# Esquematico_2.net
KiCad netlist of a schematic drawn in Altium Designer
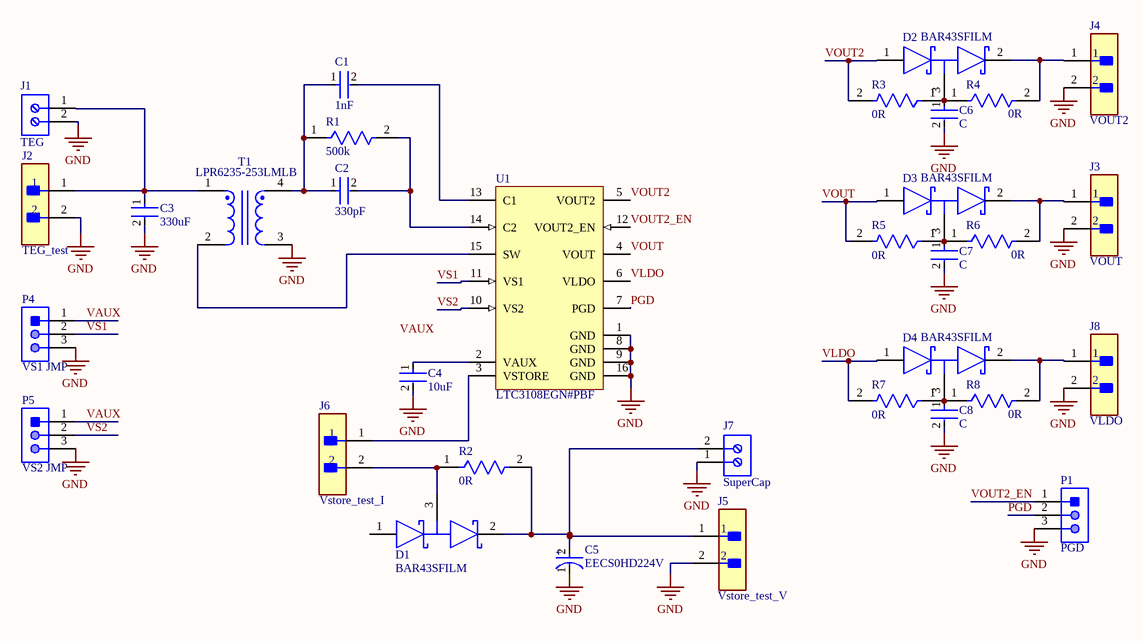
[diagram p0: Esquematico_2.SchDoc]

(export (version "E")
  (design (tool "Eeschema 10.0.6"))
  (components
    (comp (ref "C1")
      (value "1nF")
      (footprint "FP-CL21-IPC_B")
      (description "CL21 Series 0805 22uF 6.3V ±20% Tolerance X5R Multilayer Ceramic Chip Capacitor")
      (fields (field (name "TOLERANCE") "20%"))
      (libsource (lib "Altium Content Vault") (part "b4654b650e69147ec39a6b967a45e02"))
    )
    (comp (ref "C2")
      (value "330pF")
      (footprint "FP-CL21-IPC_B")
      (description "CL21 Series 0805 22uF 6.3V ±20% Tolerance X5R Multilayer Ceramic Chip Capacitor")
      (fields (field (name "TOLERANCE") "20%"))
      (libsource (lib "Altium Content Vault") (part "b4654b650e69147ec39a6b967a45e02"))
    )
    (comp (ref "C3")
      (value "330uF")
      (footprint "FP-GRM32E-0_3-MFG")
      (description "Chip Multilayer Ceramic Capacitors for General Purpose, 1210, 330uF, X5R, 15%, 20%, 4V")
      (fields (field (name "TOLERANCE") "20%"))
      (libsource (lib "Altium Content Vault") (part "b4654b650e69147ec39a6b967a45e02"))
    )
    (comp (ref "C4")
      (value "10uF")
      (footprint "FP-CL21-IPC_B")
      (description "CL21 Series 0805 22uF 6.3V ±20% Tolerance X5R Multilayer Ceramic Chip Capacitor")
      (fields (field (name "TOLERANCE") "20%"))
      (libsource (lib "Altium Content Vault") (part "b4654b650e69147ec39a6b967a45e02"))
    )
    (comp (ref "C5")
      (value "EECS0HD224V")
      (footprint "FP-EECS0HD224V-MFG")
      (description "CAP 220MF -20% +80% 5.5V T/H")
      (fields (field (name "TOLERANCE") "80%") (field (name "VOLTAGE") "500V"))
      (libsource (lib "Altium Content Vault") (part "203bc49f2ac43e59fd269a8c329ed05"))
    )
    (comp (ref "C6")
      (value "C")
      (footprint "FP-CL21-IPC_B")
      (description "CL21 Series 0805 22uF 6.3V ±20% Tolerance X5R Multilayer Ceramic Chip Capacitor")
      (fields (field (name "TOLERANCE") "20%"))
      (libsource (lib "Altium Content Vault") (part "b4654b650e69147ec39a6b967a45e02"))
    )
    (comp (ref "C7")
      (value "C")
      (footprint "FP-CL21-IPC_B")
      (description "CL21 Series 0805 22uF 6.3V ±20% Tolerance X5R Multilayer Ceramic Chip Capacitor")
      (fields (field (name "TOLERANCE") "20%"))
      (libsource (lib "Altium Content Vault") (part "b4654b650e69147ec39a6b967a45e02"))
    )
    (comp (ref "C8")
      (value "C")
      (footprint "FP-CL21-IPC_B")
      (description "CL21 Series 0805 22uF 6.3V ±20% Tolerance X5R Multilayer Ceramic Chip Capacitor")
      (fields (field (name "TOLERANCE") "20%"))
      (libsource (lib "Altium Content Vault") (part "b4654b650e69147ec39a6b967a45e02"))
    )
    (comp (ref "D1")
      (value "BAR43SFILM")
      (footprint "FP-SOT23-3L-MFG")
      (description "DIODE ARRAY SCHOTTKY 30V SOT23-3")
      (fields
        (field (name "OCTOPART") "https://octopart.com/bar43sfilm-stmicroelectronics-39549077")
        (field (name "MANUFACTURER") "STMicroelectronics")
      )
      (libsource (lib "Altium Content Vault") (part "40b30d93e5a6a7636437c253f9b461d"))
    )
    (comp (ref "D2")
      (value "BAR43SFILM")
      (footprint "FP-SOT23-3L-MFG")
      (description "DIODE ARRAY SCHOTTKY 30V SOT23-3")
      (fields
        (field (name "OCTOPART") "https://octopart.com/bar43sfilm-stmicroelectronics-39549077")
        (field (name "MANUFACTURER") "STMicroelectronics")
      )
      (libsource (lib "Altium Content Vault") (part "40b30d93e5a6a7636437c253f9b461d"))
    )
    (comp (ref "D3")
      (value "BAR43SFILM")
      (footprint "FP-SOT23-3L-MFG")
      (description "DIODE ARRAY SCHOTTKY 30V SOT23-3")
      (fields
        (field (name "OCTOPART") "https://octopart.com/bar43sfilm-stmicroelectronics-39549077")
        (field (name "MANUFACTURER") "STMicroelectronics")
      )
      (libsource (lib "Altium Content Vault") (part "40b30d93e5a6a7636437c253f9b461d"))
    )
    (comp (ref "D4")
      (value "BAR43SFILM")
      (footprint "FP-SOT23-3L-MFG")
      (description "DIODE ARRAY SCHOTTKY 30V SOT23-3")
      (fields
        (field (name "OCTOPART") "https://octopart.com/bar43sfilm-stmicroelectronics-39549077")
        (field (name "MANUFACTURER") "STMicroelectronics")
      )
      (libsource (lib "Altium Content Vault") (part "40b30d93e5a6a7636437c253f9b461d"))
    )
    (comp (ref "J1")
      (value "TEG")
      (footprint "691102710002")
      (description "Series 102 - 5.00 mm Horizontal Entry Modular with Pressure Clamp WR-TBL, 2 pin")
      (fields
        (field (name "MANUFACTURER") "Wurth Elektronik")
        (field (name "PART NUMBER") "691102710002")
        (field (name "PUBLISHER") "WurthElektronik")
      )
      (libsource (lib "") (part "WE-CN-1P-F-TB2_1"))
    )
    (comp (ref "J2")
      (value "TEG_test")
      (footprint "FP-TSW-102-07-L-S-MFG")
      (description "CONN HEADER VERT 2POS 2.54MM")
      (libsource (lib "Altium Content Vault") (part "3bc925449376181038e59eaffc5286c"))
    )
    (comp (ref "J3")
      (value "VOUT")
      (footprint "FP-TSW-102-07-L-S-MFG")
      (description "CONN HEADER VERT 2POS 2.54MM")
      (libsource (lib "") (part "3bc925449376181038e59eaffc5286c_1"))
    )
    (comp (ref "J4")
      (value "VOUT2")
      (footprint "FP-TSW-102-07-L-S-MFG")
      (description "CONN HEADER VERT 2POS 2.54MM")
      (libsource (lib "") (part "3bc925449376181038e59eaffc5286c_1"))
    )
    (comp (ref "J5")
      (value "Vstore_test_V")
      (footprint "FP-TSW-102-07-L-S-MFG")
      (description "CONN HEADER VERT 2POS 2.54MM")
      (libsource (lib "") (part "3bc925449376181038e59eaffc5286c_1"))
    )
    (comp (ref "J6")
      (value "Vstore_test_I")
      (footprint "FP-TSW-102-07-L-S-MFG")
      (description "CONN HEADER VERT 2POS 2.54MM")
      (libsource (lib "Altium Content Vault") (part "3bc925449376181038e59eaffc5286c"))
    )
    (comp (ref "J7")
      (value "SuperCap")
      (footprint "691102710002")
      (description "Series 102 - 5.00 mm Horizontal Entry Modular with Pressure Clamp WR-TBL, 2 pin")
      (fields
        (field (name "MANUFACTURER") "Wurth Elektronik")
        (field (name "PART NUMBER") "691102710002")
        (field (name "PUBLISHER") "WurthElektronik")
      )
      (libsource (lib "Altium Content Vault") (part "WE-CN-1P-F-TB2"))
    )
    (comp (ref "J8")
      (value "VLDO")
      (footprint "FP-TSW-102-07-L-S-MFG")
      (description "CONN HEADER VERT 2POS 2.54MM")
      (libsource (lib "") (part "3bc925449376181038e59eaffc5286c_1"))
    )
    (comp (ref "P1")
      (value "PGD")
      (footprint "MOLX-22-28-4033_V")
      (description "Male Header, Pitch 2.54 mm, 1 x 3 Position, Height 8.38 mm, Tail Length 3.18 mm, RoHS, Bulk")
      (fields (field (name "MANUFACTURER") "Molex"))
      (libsource (lib "") (part "CN-1P-M-R3_1"))
    )
    (comp (ref "P4")
      (value "VS1 JMP")
      (footprint "MOLX-22-28-4033_V")
      (description "Male Header, Pitch 2.54 mm, 1 x 3 Position, Height 8.38 mm, Tail Length 3.18 mm, RoHS, Bulk")
      (fields (field (name "MANUFACTURER") "Molex"))
      (libsource (lib "Altium Content Vault") (part "CN-1P-M-R3"))
    )
    (comp (ref "P5")
      (value "VS2 JMP")
      (footprint "MOLX-22-28-4033_V")
      (description "Male Header, Pitch 2.54 mm, 1 x 3 Position, Height 8.38 mm, Tail Length 3.18 mm, RoHS, Bulk")
      (fields (field (name "MANUFACTURER") "Molex"))
      (libsource (lib "Altium Content Vault") (part "CN-1P-M-R3"))
    )
    (comp (ref "R1")
      (value "500k")
      (footprint "FP-RP732A-IPC_C")
      (fields (field (name "TOLERANCE") "0.1%"))
      (libsource (lib "Altium Content Vault") (part "1029c3af85768c4190bb7ad29bc67b5"))
    )
    (comp (ref "R2")
      (value "0R")
      (footprint "FP-RP732A-IPC_C")
      (fields (field (name "TOLERANCE") "0.1%"))
      (libsource (lib "Altium Content Vault") (part "1029c3af85768c4190bb7ad29bc67b5"))
    )
    (comp (ref "R3")
      (value "0R")
      (footprint "FP-RP732A-IPC_C")
      (fields (field (name "TOLERANCE") "0.1%"))
      (libsource (lib "Altium Content Vault") (part "1029c3af85768c4190bb7ad29bc67b5"))
    )
    (comp (ref "R4")
      (value "0R")
      (footprint "FP-RP732A-IPC_C")
      (fields (field (name "TOLERANCE") "0.1%"))
      (libsource (lib "Altium Content Vault") (part "1029c3af85768c4190bb7ad29bc67b5"))
    )
    (comp (ref "R5")
      (value "0R")
      (footprint "FP-RP732A-IPC_C")
      (fields (field (name "TOLERANCE") "0.1%"))
      (libsource (lib "Altium Content Vault") (part "1029c3af85768c4190bb7ad29bc67b5"))
    )
    (comp (ref "R6")
      (value "0R")
      (footprint "FP-RP732A-IPC_C")
      (fields (field (name "TOLERANCE") "0.1%"))
      (libsource (lib "Altium Content Vault") (part "1029c3af85768c4190bb7ad29bc67b5"))
    )
    (comp (ref "R7")
      (value "0R")
      (footprint "FP-RP732A-IPC_C")
      (fields (field (name "TOLERANCE") "0.1%"))
      (libsource (lib "Altium Content Vault") (part "1029c3af85768c4190bb7ad29bc67b5"))
    )
    (comp (ref "R8")
      (value "0R")
      (footprint "FP-RP732A-IPC_C")
      (fields (field (name "TOLERANCE") "0.1%"))
      (libsource (lib "Altium Content Vault") (part "1029c3af85768c4190bb7ad29bc67b5"))
    )
    (comp (ref "T1")
      (value "LPR6235-253LMLB")
      (footprint "FP-LPR6235-MFG")
      (description "Coupled Inductors Mini Step-up Xfmr SEE PART COMMENT TAB")
      (fields
        (field (name "MANUFACTURER") "Coilcraft")
        (field (name "OCTOPART") "https://octopart.com/lpr6235-253lmlb-coilcraft-14935593")
      )
      (libsource (lib "Altium Content Vault") (part "ea91485b871619091096948d5d39144"))
    )
    (comp (ref "U1")
      (value "LTC3108EGN#PBF")
      (footprint "LT-GN-16_M")
      (description "Ultralow Voltage Step-Up Converter and Power Manager, 16-pin SOP (GN-16), -40 to 125 degC, Pb-Free")
      (fields (field (name "MANUFACTURER") "Linear Technology"))
      (libsource (lib "Altium Content Vault") (part "LT-LTC3108-X-GN-16"))
    )
  )
  (nets
    (net (code "1") (name "/PGD") (class "Default")
      (node (ref "P1") (pin "2") (pinfunction "2_2") (pintype "passive"))
      (node (ref "U1") (pin "7") (pinfunction "PGD_7") (pintype "open_collector"))
    )
    (net (code "2") (name "/VAUX") (class "Default")
      (node (ref "P4") (pin "1") (pinfunction "1_1") (pintype "passive"))
      (node (ref "P5") (pin "1") (pinfunction "1_1") (pintype "passive"))
    )
    (net (code "3") (name "/VLDO") (class "Default")
      (node (ref "D4") (pin "1") (pinfunction "A2_1") (pintype "passive"))
      (node (ref "R7") (pin "2") (pinfunction "2_2") (pintype "passive"))
      (node (ref "U1") (pin "6") (pinfunction "VLDO_6") (pintype "power_in"))
    )
    (net (code "4") (name "/VOUT") (class "Default")
      (node (ref "D3") (pin "1") (pinfunction "A2_1") (pintype "passive"))
      (node (ref "R5") (pin "2") (pinfunction "2_2") (pintype "passive"))
      (node (ref "U1") (pin "4") (pinfunction "VOUT_4") (pintype "power_in"))
    )
    (net (code "5") (name "/VOUT2") (class "Default")
      (node (ref "D2") (pin "1") (pinfunction "A2_1") (pintype "passive"))
      (node (ref "R3") (pin "2") (pinfunction "2_2") (pintype "passive"))
      (node (ref "U1") (pin "5") (pinfunction "VOUT2_5") (pintype "power_in"))
    )
    (net (code "6") (name "/VOUT2_EN") (class "Default")
      (node (ref "P1") (pin "1") (pinfunction "1_1") (pintype "passive"))
      (node (ref "U1") (pin "12") (pinfunction "VOUT2_EN_12") (pintype "input"))
    )
    (net (code "7") (name "/VS1") (class "Default")
      (node (ref "P4") (pin "2") (pinfunction "2_2") (pintype "passive"))
      (node (ref "U1") (pin "11") (pinfunction "VS1_11") (pintype "input"))
    )
    (net (code "8") (name "/VS2") (class "Default")
      (node (ref "P5") (pin "2") (pinfunction "2_2") (pintype "passive"))
      (node (ref "U1") (pin "10") (pinfunction "VS2_10") (pintype "input"))
    )
    (net (code "9") (name "GND") (class "Default")
      (node (ref "C3") (pin "2") (pinfunction "2_2") (pintype "passive"))
      (node (ref "C4") (pin "2") (pinfunction "2_2") (pintype "passive"))
      (node (ref "C5") (pin "1") (pinfunction "C_1") (pintype "passive"))
      (node (ref "C6") (pin "2") (pinfunction "2_2") (pintype "passive"))
      (node (ref "C7") (pin "2") (pinfunction "2_2") (pintype "passive"))
      (node (ref "C8") (pin "2") (pinfunction "2_2") (pintype "passive"))
      (node (ref "J1") (pin "2") (pinfunction "2_2") (pintype "passive"))
      (node (ref "J2") (pin "2") (pinfunction "2_2") (pintype "passive"))
      (node (ref "J3") (pin "2") (pinfunction "2_2") (pintype "passive"))
      (node (ref "J4") (pin "2") (pinfunction "2_2") (pintype "passive"))
      (node (ref "J5") (pin "2") (pinfunction "2_2") (pintype "passive"))
      (node (ref "J7") (pin "1") (pinfunction "1_1") (pintype "passive"))
      (node (ref "J8") (pin "2") (pinfunction "2_2") (pintype "passive"))
      (node (ref "P1") (pin "3") (pinfunction "3_3") (pintype "passive"))
      (node (ref "P4") (pin "3") (pinfunction "3_3") (pintype "passive"))
      (node (ref "P5") (pin "3") (pinfunction "3_3") (pintype "passive"))
      (node (ref "T1") (pin "3") (pinfunction "3_3") (pintype "passive"))
      (node (ref "U1") (pin "1") (pinfunction "GND_1") (pintype "power_in"))
      (node (ref "U1") (pin "16") (pinfunction "GND_16") (pintype "power_in"))
      (node (ref "U1") (pin "8") (pinfunction "GND_8") (pintype "power_in"))
      (node (ref "U1") (pin "9") (pinfunction "GND_9") (pintype "power_in"))
    )
    (net (code "10") (name "Net-(C1-Pad1)") (class "Default")
      (node (ref "C1") (pin "1") (pinfunction "1_1") (pintype "passive"))
      (node (ref "C2") (pin "1") (pinfunction "1_1") (pintype "passive"))
      (node (ref "R1") (pin "1") (pinfunction "1_1") (pintype "passive"))
      (node (ref "T1") (pin "4") (pinfunction "4_4") (pintype "passive"))
    )
    (net (code "11") (name "Net-(C3-Pad1)") (class "Default")
      (node (ref "C3") (pin "1") (pinfunction "1_1") (pintype "passive"))
      (node (ref "J1") (pin "1") (pinfunction "1_1") (pintype "passive"))
      (node (ref "J2") (pin "1") (pinfunction "1_1") (pintype "passive"))
      (node (ref "T1") (pin "1") (pinfunction "1_1") (pintype "passive"))
    )
    (net (code "12") (name "Net-(C5-A)") (class "Default")
      (node (ref "C5") (pin "2") (pinfunction "A_2") (pintype "passive"))
      (node (ref "D1") (pin "2") (pinfunction "K1_2") (pintype "passive"))
      (node (ref "J5") (pin "1") (pinfunction "1_1") (pintype "passive"))
      (node (ref "J7") (pin "2") (pinfunction "2_2") (pintype "passive"))
      (node (ref "R2") (pin "2") (pinfunction "2_2") (pintype "passive"))
    )
    (net (code "13") (name "Net-(D1-A1{slash}K2)") (class "Default")
      (node (ref "D1") (pin "3") (pinfunction "A1/K2_3") (pintype "passive"))
      (node (ref "J6") (pin "2") (pinfunction "2_2") (pintype "passive"))
      (node (ref "R2") (pin "1") (pinfunction "1_1") (pintype "passive"))
    )
    (net (code "14") (name "Net-(D2-A1{slash}K2)") (class "Default")
      (node (ref "C6") (pin "1") (pinfunction "1_1") (pintype "passive"))
      (node (ref "D2") (pin "3") (pinfunction "A1/K2_3") (pintype "passive"))
      (node (ref "R3") (pin "1") (pinfunction "1_1") (pintype "passive"))
      (node (ref "R4") (pin "1") (pinfunction "1_1") (pintype "passive"))
    )
    (net (code "15") (name "Net-(D2-K1)") (class "Default")
      (node (ref "D2") (pin "2") (pinfunction "K1_2") (pintype "passive"))
      (node (ref "J4") (pin "1") (pinfunction "1_1") (pintype "passive"))
      (node (ref "R4") (pin "2") (pinfunction "2_2") (pintype "passive"))
    )
    (net (code "16") (name "Net-(D3-A1{slash}K2)") (class "Default")
      (node (ref "C7") (pin "1") (pinfunction "1_1") (pintype "passive"))
      (node (ref "D3") (pin "3") (pinfunction "A1/K2_3") (pintype "passive"))
      (node (ref "R5") (pin "1") (pinfunction "1_1") (pintype "passive"))
      (node (ref "R6") (pin "1") (pinfunction "1_1") (pintype "passive"))
    )
    (net (code "17") (name "Net-(D3-K1)") (class "Default")
      (node (ref "D3") (pin "2") (pinfunction "K1_2") (pintype "passive"))
      (node (ref "J3") (pin "1") (pinfunction "1_1") (pintype "passive"))
      (node (ref "R6") (pin "2") (pinfunction "2_2") (pintype "passive"))
    )
    (net (code "18") (name "Net-(D4-A1{slash}K2)") (class "Default")
      (node (ref "C8") (pin "1") (pinfunction "1_1") (pintype "passive"))
      (node (ref "D4") (pin "3") (pinfunction "A1/K2_3") (pintype "passive"))
      (node (ref "R7") (pin "1") (pinfunction "1_1") (pintype "passive"))
      (node (ref "R8") (pin "1") (pinfunction "1_1") (pintype "passive"))
    )
    (net (code "19") (name "Net-(D4-K1)") (class "Default")
      (node (ref "D4") (pin "2") (pinfunction "K1_2") (pintype "passive"))
      (node (ref "J8") (pin "1") (pinfunction "1_1") (pintype "passive"))
      (node (ref "R8") (pin "2") (pinfunction "2_2") (pintype "passive"))
    )
    (net (code "20") (name "Net-(U1-C1)") (class "Default")
      (node (ref "C1") (pin "2") (pinfunction "2_2") (pintype "passive"))
      (node (ref "U1") (pin "13") (pinfunction "C1_13") (pintype "power_in"))
    )
    (net (code "21") (name "Net-(U1-C2)") (class "Default")
      (node (ref "C2") (pin "2") (pinfunction "2_2") (pintype "passive"))
      (node (ref "R1") (pin "2") (pinfunction "2_2") (pintype "passive"))
      (node (ref "U1") (pin "14") (pinfunction "C2_14") (pintype "input"))
    )
    (net (code "22") (name "Net-(U1-SW)") (class "Default")
      (node (ref "T1") (pin "2") (pinfunction "2_2") (pintype "passive"))
      (node (ref "U1") (pin "15") (pinfunction "SW_15") (pintype "power_in"))
    )
    (net (code "23") (name "Net-(U1-VAUX)") (class "Default")
      (node (ref "C4") (pin "1") (pinfunction "1_1") (pintype "passive"))
      (node (ref "U1") (pin "2") (pinfunction "VAUX_2") (pintype "power_in"))
    )
    (net (code "24") (name "Net-(U1-VSTORE)") (class "Default")
      (node (ref "J6") (pin "1") (pinfunction "1_1") (pintype "passive"))
      (node (ref "U1") (pin "3") (pinfunction "VSTORE_3") (pintype "power_in"))
    )
    (net (code "25") (name "unconnected-(D1-A2-Pad1)") (class "Default")
      (node (ref "D1") (pin "1") (pinfunction "A2_1") (pintype "passive"))
    )
  )
)
